# MCU.net
KiCad netlist of a schematic drawn in Altium Designer
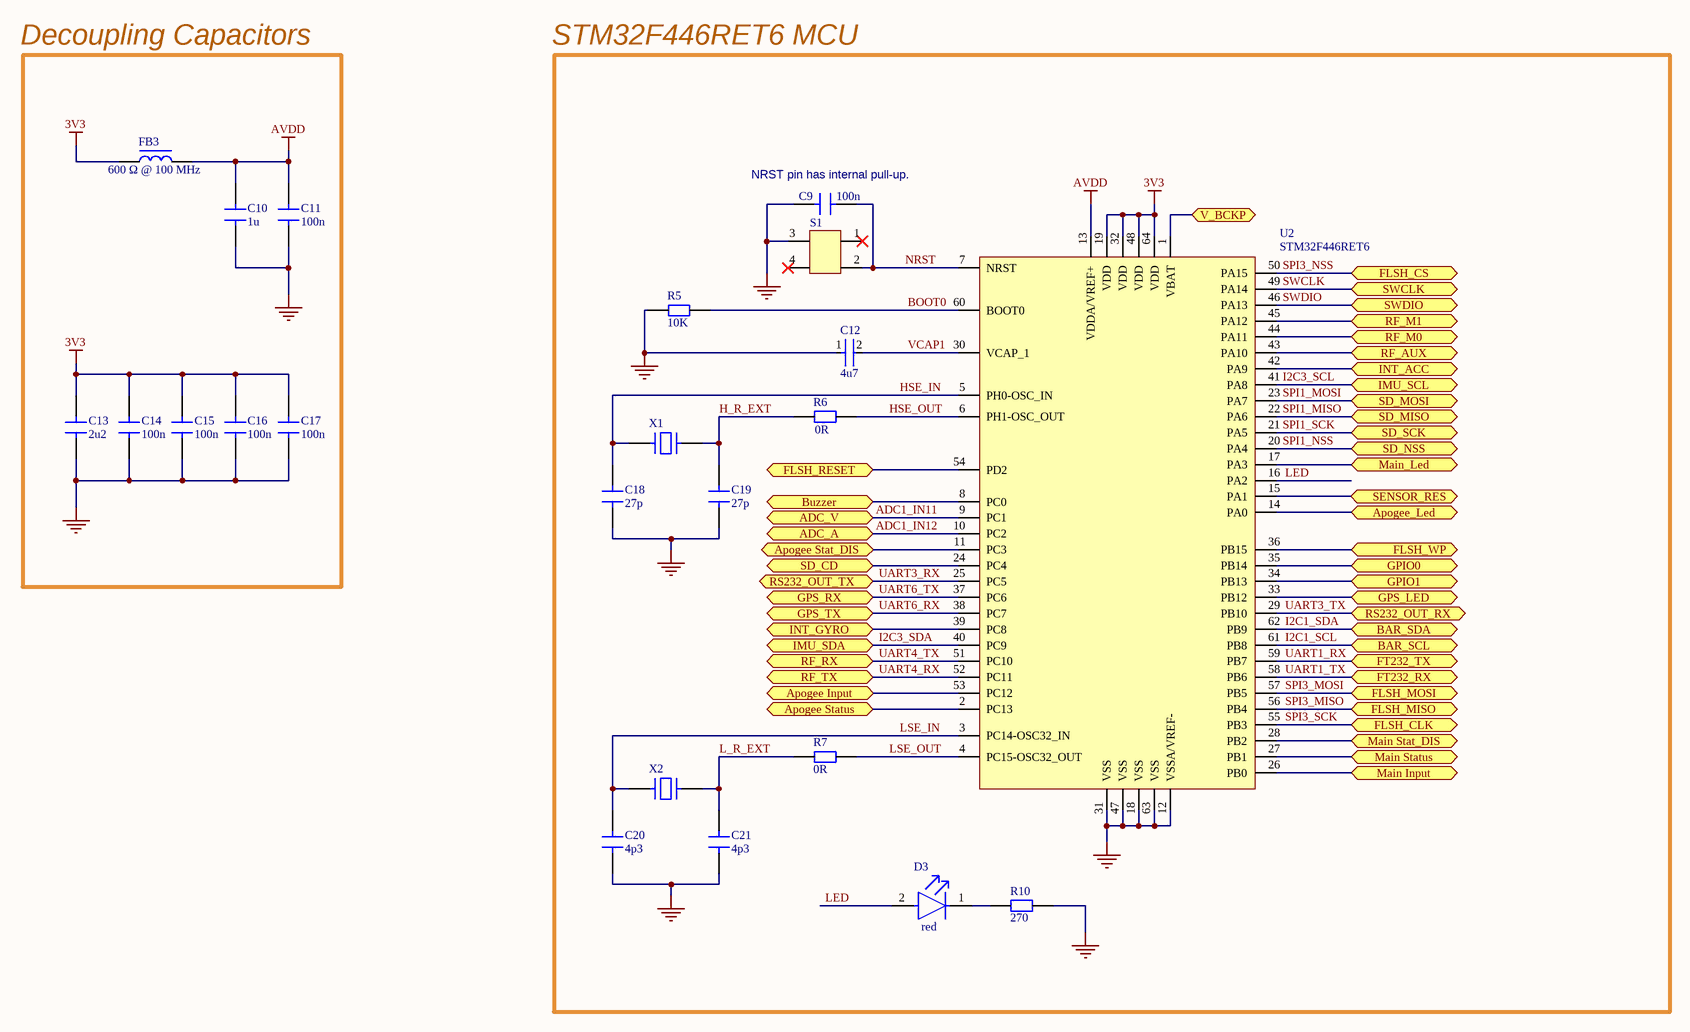
[diagram p0: MCU.SchDoc]

(export (version "E")
  (design (tool "Eeschema 10.0.6"))
  (components
    (comp (ref "C9")
      (value "100n")
      (footprint "CAP 0603")
      (description "Capacitor SMD 0603 50V")
      (libsource (lib "Schlib") (part "CAP 0603 50V"))
    )
    (comp (ref "C10")
      (value "1u")
      (footprint "CAP 0805")
      (description "Capacitor SMD 0805 50V")
      (libsource (lib "Schlib") (part "CAP 0805 50V"))
    )
    (comp (ref "C11")
      (value "100n")
      (footprint "CAP 0805")
      (description "Capacitor SMD 0805 50V")
      (libsource (lib "R_07_24-Schlib") (part "CAP 0805 50V"))
    )
    (comp (ref "C12")
      (value "4u7")
      (footprint "FP-1206-L_3_2_0_2-W_1_6_0-IPC_A")
      (description "None")
      (fields (field (name "TOLERANCE") "20%"))
      (libsource (lib "Altium Content Vault") (part "b4654b650e69147ec39a6b967a45e02"))
    )
    (comp (ref "C13")
      (value "2u2")
      (footprint "CAP 0805")
      (description "Capacitor SMD 0805 25V")
      (libsource (lib "Schlib") (part "CAP 0805 25V"))
    )
    (comp (ref "C14")
      (value "100n")
      (footprint "CAP 0805")
      (description "Capacitor SMD 0805 50V")
      (libsource (lib "R_07_24-Schlib") (part "CAP 0805 50V"))
    )
    (comp (ref "C15")
      (value "100n")
      (footprint "CAP 0805")
      (description "Capacitor SMD 0805 50V")
      (libsource (lib "R_07_24-Schlib") (part "CAP 0805 50V"))
    )
    (comp (ref "C16")
      (value "100n")
      (footprint "CAP 0805")
      (description "Capacitor SMD 0805 50V")
      (libsource (lib "R_07_24-Schlib") (part "CAP 0805 50V"))
    )
    (comp (ref "C17")
      (value "100n")
      (footprint "CAP 0805")
      (description "Capacitor SMD 0805 50V")
      (libsource (lib "R_07_24-Schlib") (part "CAP 0805 50V"))
    )
    (comp (ref "C18")
      (value "27p")
      (footprint "CAP 0805")
      (description "Capacitor SMD 0805 50V")
      (libsource (lib "R_07_24-Schlib") (part "CAP 0805 50V"))
    )
    (comp (ref "C19")
      (value "27p")
      (footprint "CAP 0805")
      (description "Capacitor SMD 0805 50V")
      (libsource (lib "R_07_24-Schlib") (part "CAP 0805 50V"))
    )
    (comp (ref "C20")
      (value "4p3")
      (footprint "CAP 0805")
      (description "Capacitor SMD 0805 50V")
      (libsource (lib "R_07_24-Schlib") (part "CAP 0805 50V"))
    )
    (comp (ref "C21")
      (value "4p3")
      (footprint "CAP 0805")
      (description "Capacitor SMD 0805 50V")
      (libsource (lib "R_07_24-Schlib") (part "CAP 0805 50V"))
    )
    (comp (ref "D3")
      (value "red")
      (footprint "FP-LTST-C170GKT-MFG")
      (description "LED GREEN CLEAR SMD")
      (fields (field (name "VOLTAGE") "5V"))
      (libsource (lib "Altium Content Vault") (part "8706943c75ba83719d021d2fdc84c58"))
    )
    (comp (ref "FB3")
      (value "600 Ω @ 100 MHz")
      (footprint "FB 0805")
      (description "Ferrite Bead SMD 0805")
      (libsource (lib "Schlib") (part "FB 0805"))
    )
    (comp (ref "R5")
      (value "10K")
      (footprint "RES 0805")
      (description "Resistor SMD 0805")
      (libsource (lib "R_07_24-Schlib") (part "RES 0805"))
    )
    (comp (ref "R6")
      (value "0R")
      (footprint "RES 0805")
      (description "Resistor SMD 0805")
      (libsource (lib "R_07_24-Schlib") (part "RES 0805"))
    )
    (comp (ref "R7")
      (value "0R")
      (footprint "RES 0805")
      (description "Resistor SMD 0805")
      (libsource (lib "R_07_24-Schlib") (part "RES 0805"))
    )
    (comp (ref "R10")
      (value "270")
      (footprint "RES 0805")
      (description "Resistor SMD 0805")
      (libsource (lib "R_07_24-Schlib") (part "RES 0805"))
    )
    (comp (ref "S1")
      (value "FSM4JSMATR")
      (footprint "FSM4JSMATR")
      (description "Switch Tactile OFF (ON) SPST Round Button Gull Wing 0.05A 24VDC 1.57N SMD T/R")
      (fields (field (name "MANUFACTURER") "TE Connectivity Alcoswitch"))
      (libsource (lib "Schlib") (part "FSM4JSMATR"))
    )
    (comp (ref "U2")
      (value "STM32F446RET6")
      (footprint "STM32F446RET6")
      (description "ARM® Cortex®-M4 STM32 F4 Microcontroller IC 32-Bit 180MHz 512KB (512K x 8) FLASH 64-LQFP (10x10)")
      (fields (field (name "MANUFACTURER") "STMicroelectronics"))
      (libsource (lib "Schlib") (part "STM32F446RET6"))
    )
    (comp (ref "X1")
      (value "ABM3-8.000MHZ-D2Y-T")
      (footprint "ABM3-8.000MHZ-D2Y-T")
      (description "Crystal 8MHz ±20ppm (Tol) ±30ppm (Stability) 18pF FUND 140Ohm 2-Pin Mini-CSMD T/R")
      (fields (field (name "MANUFACTURER") "Abracon"))
      (libsource (lib "Schlib") (part "ABM3-8.000MHZ-D2Y-T"))
    )
    (comp (ref "X2")
      (value "ABS25-32.768KHZ-6-T")
      (footprint "ABS25-32.768KHZ-6-T")
      (description "Crystal, Plastic Molded 32.768Khz, 6Pf, 20Ppm-40+85C, 8 X 3.8 X 2.5 Rohs Compliant: Yes")
      (fields (field (name "MANUFACTURER") "Abracon"))
      (libsource (lib "Schlib") (part "ABS25-32.768KHZ-6-T"))
    )
  )
  (nets
    (net (code "1") (name "/ADC1_IN11") (class "Default")
      (node (ref "U2") (pin "9") (pinfunction "PC1_9") (pintype "passive"))
    )
    (net (code "2") (name "/ADC1_IN12") (class "Default")
      (node (ref "U2") (pin "10") (pinfunction "PC2_10") (pintype "passive"))
    )
    (net (code "3") (name "/Apogee Input") (class "Default")
      (node (ref "U2") (pin "53") (pinfunction "PC12_53") (pintype "passive"))
    )
    (net (code "4") (name "/Apogee Stat_DIS") (class "Default")
      (node (ref "U2") (pin "11") (pinfunction "PC3_11") (pintype "passive"))
    )
    (net (code "5") (name "/Apogee Status") (class "Default")
      (node (ref "U2") (pin "2") (pinfunction "PC13_2") (pintype "passive"))
    )
    (net (code "6") (name "/Apogee_Led") (class "Default")
      (node (ref "U2") (pin "14") (pinfunction "PA0_14") (pintype "passive"))
    )
    (net (code "7") (name "/BOOT0") (class "Default")
      (node (ref "R5") (pin "2") (pinfunction "2_2") (pintype "passive"))
      (node (ref "U2") (pin "60") (pinfunction "BOOT0_60") (pintype "passive"))
    )
    (net (code "8") (name "/Buzzer") (class "Default")
      (node (ref "U2") (pin "8") (pinfunction "PC0_8") (pintype "passive"))
    )
    (net (code "9") (name "/FLSH_RESET") (class "Default")
      (node (ref "U2") (pin "54") (pinfunction "PD2_54") (pintype "passive"))
    )
    (net (code "10") (name "/FLSH_WP") (class "Default")
      (node (ref "U2") (pin "36") (pinfunction "PB15_36") (pintype "passive"))
    )
    (net (code "11") (name "/GPIO0") (class "Default")
      (node (ref "U2") (pin "35") (pinfunction "PB14_35") (pintype "passive"))
    )
    (net (code "12") (name "/GPIO1") (class "Default")
      (node (ref "U2") (pin "34") (pinfunction "PB13_34") (pintype "passive"))
    )
    (net (code "13") (name "/GPS_LED") (class "Default")
      (node (ref "U2") (pin "33") (pinfunction "PB12_33") (pintype "passive"))
    )
    (net (code "14") (name "/HSE_IN") (class "Default")
      (node (ref "C18") (pin "2") (pinfunction "2_2") (pintype "passive"))
      (node (ref "U2") (pin "5") (pinfunction "PH0-OSC_IN_5") (pintype "passive"))
      (node (ref "X1") (pin "1") (pinfunction "1_1") (pintype "passive"))
    )
    (net (code "15") (name "/HSE_OUT") (class "Default")
      (node (ref "R6") (pin "2") (pinfunction "2_2") (pintype "passive"))
      (node (ref "U2") (pin "6") (pinfunction "PH1-OSC_OUT_6") (pintype "passive"))
    )
    (net (code "16") (name "/H_R_EXT") (class "Default")
      (node (ref "C19") (pin "2") (pinfunction "2_2") (pintype "passive"))
      (node (ref "R6") (pin "1") (pinfunction "1_1") (pintype "passive"))
      (node (ref "X1") (pin "2") (pinfunction "2_2") (pintype "passive"))
    )
    (net (code "17") (name "/I2C1_SCL") (class "Default")
      (node (ref "U2") (pin "61") (pinfunction "PB8_61") (pintype "passive"))
    )
    (net (code "18") (name "/I2C1_SDA") (class "Default")
      (node (ref "U2") (pin "62") (pinfunction "PB9_62") (pintype "passive"))
    )
    (net (code "19") (name "/I2C3_SCL") (class "Default")
      (node (ref "U2") (pin "41") (pinfunction "PA8_41") (pintype "passive"))
    )
    (net (code "20") (name "/I2C3_SDA") (class "Default")
      (node (ref "U2") (pin "40") (pinfunction "PC9_40") (pintype "passive"))
    )
    (net (code "21") (name "/INT_ACC") (class "Default")
      (node (ref "U2") (pin "42") (pinfunction "PA9_42") (pintype "passive"))
    )
    (net (code "22") (name "/INT_GYRO") (class "Default")
      (node (ref "U2") (pin "39") (pinfunction "PC8_39") (pintype "passive"))
    )
    (net (code "23") (name "/LED") (class "Default")
      (node (ref "D3") (pin "2") (pinfunction "A_2") (pintype "passive"))
      (node (ref "U2") (pin "16") (pinfunction "PA2_16") (pintype "passive"))
    )
    (net (code "24") (name "/LSE_IN") (class "Default")
      (node (ref "C20") (pin "2") (pinfunction "2_2") (pintype "passive"))
      (node (ref "U2") (pin "3") (pinfunction "PC14-OSC32_IN_3") (pintype "passive"))
      (node (ref "X2") (pin "1") (pinfunction "1_1") (pintype "passive"))
    )
    (net (code "25") (name "/LSE_OUT") (class "Default")
      (node (ref "R7") (pin "2") (pinfunction "2_2") (pintype "passive"))
      (node (ref "U2") (pin "4") (pinfunction "PC15-OSC32_OUT_4") (pintype "passive"))
    )
    (net (code "26") (name "/L_R_EXT") (class "Default")
      (node (ref "C21") (pin "2") (pinfunction "2_2") (pintype "passive"))
      (node (ref "R7") (pin "1") (pinfunction "1_1") (pintype "passive"))
      (node (ref "X2") (pin "4") (pinfunction "4_4") (pintype "passive"))
    )
    (net (code "27") (name "/Main Input") (class "Default")
      (node (ref "U2") (pin "26") (pinfunction "PB0_26") (pintype "passive"))
    )
    (net (code "28") (name "/Main Stat_DIS") (class "Default")
      (node (ref "U2") (pin "28") (pinfunction "PB2_28") (pintype "passive"))
    )
    (net (code "29") (name "/Main Status") (class "Default")
      (node (ref "U2") (pin "27") (pinfunction "PB1_27") (pintype "passive"))
    )
    (net (code "30") (name "/Main_Led") (class "Default")
      (node (ref "U2") (pin "17") (pinfunction "PA3_17") (pintype "passive"))
    )
    (net (code "31") (name "/NRST") (class "Default")
      (node (ref "C9") (pin "2") (pinfunction "2_2") (pintype "passive"))
      (node (ref "S1") (pin "2") (pinfunction "2_2") (pintype "passive"))
      (node (ref "U2") (pin "7") (pinfunction "NRST_7") (pintype "passive"))
    )
    (net (code "32") (name "/RF_AUX") (class "Default")
      (node (ref "U2") (pin "43") (pinfunction "PA10_43") (pintype "passive"))
    )
    (net (code "33") (name "/RF_M0") (class "Default")
      (node (ref "U2") (pin "44") (pinfunction "PA11_44") (pintype "passive"))
    )
    (net (code "34") (name "/RF_M1") (class "Default")
      (node (ref "U2") (pin "45") (pinfunction "PA12_45") (pintype "passive"))
    )
    (net (code "35") (name "/SD_CD") (class "Default")
      (node (ref "U2") (pin "24") (pinfunction "PC4_24") (pintype "passive"))
    )
    (net (code "36") (name "/SENSOR_RES") (class "Default")
      (node (ref "U2") (pin "15") (pinfunction "PA1_15") (pintype "passive"))
    )
    (net (code "37") (name "/SPI1_MISO") (class "Default")
      (node (ref "U2") (pin "22") (pinfunction "PA6_22") (pintype "passive"))
    )
    (net (code "38") (name "/SPI1_MOSI") (class "Default")
      (node (ref "U2") (pin "23") (pinfunction "PA7_23") (pintype "passive"))
    )
    (net (code "39") (name "/SPI1_NSS") (class "Default")
      (node (ref "U2") (pin "20") (pinfunction "PA4_20") (pintype "passive"))
    )
    (net (code "40") (name "/SPI1_SCK") (class "Default")
      (node (ref "U2") (pin "21") (pinfunction "PA5_21") (pintype "passive"))
    )
    (net (code "41") (name "/SPI3_MISO") (class "Default")
      (node (ref "U2") (pin "56") (pinfunction "PB4_56") (pintype "passive"))
    )
    (net (code "42") (name "/SPI3_MOSI") (class "Default")
      (node (ref "U2") (pin "57") (pinfunction "PB5_57") (pintype "passive"))
    )
    (net (code "43") (name "/SPI3_NSS") (class "Default")
      (node (ref "U2") (pin "50") (pinfunction "PA15_50") (pintype "passive"))
    )
    (net (code "44") (name "/SPI3_SCK") (class "Default")
      (node (ref "U2") (pin "55") (pinfunction "PB3_55") (pintype "passive"))
    )
    (net (code "45") (name "/SWCLK") (class "Default")
      (node (ref "U2") (pin "49") (pinfunction "PA14_49") (pintype "passive"))
    )
    (net (code "46") (name "/SWDIO") (class "Default")
      (node (ref "U2") (pin "46") (pinfunction "PA13_46") (pintype "passive"))
    )
    (net (code "47") (name "/UART1_RX") (class "Default")
      (node (ref "U2") (pin "59") (pinfunction "PB7_59") (pintype "passive"))
    )
    (net (code "48") (name "/UART1_TX") (class "Default")
      (node (ref "U2") (pin "58") (pinfunction "PB6_58") (pintype "passive"))
    )
    (net (code "49") (name "/UART3_RX") (class "Default")
      (node (ref "U2") (pin "25") (pinfunction "PC5_25") (pintype "passive"))
    )
    (net (code "50") (name "/UART3_TX") (class "Default")
      (node (ref "U2") (pin "29") (pinfunction "PB10_29") (pintype "passive"))
    )
    (net (code "51") (name "/UART4_RX") (class "Default")
      (node (ref "U2") (pin "52") (pinfunction "PC11_52") (pintype "passive"))
    )
    (net (code "52") (name "/UART4_TX") (class "Default")
      (node (ref "U2") (pin "51") (pinfunction "PC10_51") (pintype "passive"))
    )
    (net (code "53") (name "/UART6_RX") (class "Default")
      (node (ref "U2") (pin "38") (pinfunction "PC7_38") (pintype "passive"))
    )
    (net (code "54") (name "/UART6_TX") (class "Default")
      (node (ref "U2") (pin "37") (pinfunction "PC6_37") (pintype "passive"))
    )
    (net (code "55") (name "/VCAP1") (class "Default")
      (node (ref "C12") (pin "2") (pinfunction "2_2") (pintype "passive"))
      (node (ref "U2") (pin "30") (pinfunction "VCAP_1_30") (pintype "passive"))
    )
    (net (code "56") (name "/V_BCKP") (class "Default")
      (node (ref "U2") (pin "1") (pinfunction "VBAT_1") (pintype "passive"))
    )
    (net (code "57") (name "3V3") (class "Default")
      (node (ref "C13") (pin "2") (pinfunction "2_2") (pintype "passive"))
      (node (ref "C14") (pin "2") (pinfunction "2_2") (pintype "passive"))
      (node (ref "C15") (pin "2") (pinfunction "2_2") (pintype "passive"))
      (node (ref "C16") (pin "2") (pinfunction "2_2") (pintype "passive"))
      (node (ref "C17") (pin "2") (pinfunction "2_2") (pintype "passive"))
      (node (ref "FB3") (pin "1") (pintype "passive"))
      (node (ref "U2") (pin "19") (pinfunction "VDD_19") (pintype "passive"))
      (node (ref "U2") (pin "32") (pinfunction "VDD_32") (pintype "passive"))
      (node (ref "U2") (pin "48") (pinfunction "VDD_48") (pintype "passive"))
      (node (ref "U2") (pin "64") (pinfunction "VDD_64") (pintype "passive"))
    )
    (net (code "58") (name "AVDD") (class "Default")
      (node (ref "C10") (pin "2") (pinfunction "2_2") (pintype "passive"))
      (node (ref "C11") (pin "2") (pinfunction "2_2") (pintype "passive"))
      (node (ref "FB3") (pin "2") (pintype "passive"))
      (node (ref "U2") (pin "13") (pinfunction "VDDA/VREF+_13") (pintype "passive"))
    )
    (net (code "59") (name "GND") (class "Default")
      (node (ref "C10") (pin "1") (pinfunction "1_1") (pintype "passive"))
      (node (ref "C11") (pin "1") (pinfunction "1_1") (pintype "passive"))
      (node (ref "C12") (pin "1") (pinfunction "1_1") (pintype "passive"))
      (node (ref "C13") (pin "1") (pinfunction "1_1") (pintype "passive"))
      (node (ref "C14") (pin "1") (pinfunction "1_1") (pintype "passive"))
      (node (ref "C15") (pin "1") (pinfunction "1_1") (pintype "passive"))
      (node (ref "C16") (pin "1") (pinfunction "1_1") (pintype "passive"))
      (node (ref "C17") (pin "1") (pinfunction "1_1") (pintype "passive"))
      (node (ref "C18") (pin "1") (pinfunction "1_1") (pintype "passive"))
      (node (ref "C19") (pin "1") (pinfunction "1_1") (pintype "passive"))
      (node (ref "C20") (pin "1") (pinfunction "1_1") (pintype "passive"))
      (node (ref "C21") (pin "1") (pinfunction "1_1") (pintype "passive"))
      (node (ref "C9") (pin "1") (pinfunction "1_1") (pintype "passive"))
      (node (ref "R10") (pin "1") (pinfunction "1_1") (pintype "passive"))
      (node (ref "R5") (pin "1") (pinfunction "1_1") (pintype "passive"))
      (node (ref "S1") (pin "3") (pinfunction "3_3") (pintype "passive"))
      (node (ref "U2") (pin "12") (pinfunction "VSSA/VREF-_12") (pintype "passive"))
      (node (ref "U2") (pin "18") (pinfunction "VSS_18") (pintype "passive"))
      (node (ref "U2") (pin "31") (pinfunction "VSS_31") (pintype "passive"))
      (node (ref "U2") (pin "47") (pinfunction "VSS_47") (pintype "passive"))
      (node (ref "U2") (pin "63") (pinfunction "VSS_63") (pintype "passive"))
    )
    (net (code "60") (name "Net-(D3-C)") (class "Default")
      (node (ref "D3") (pin "1") (pinfunction "C_1") (pintype "passive"))
      (node (ref "R10") (pin "2") (pinfunction "2_2") (pintype "passive"))
    )
    (net (code "61") (name "unconnected-(S1-Pad1)") (class "Default")
      (node (ref "S1") (pin "1") (pinfunction "1_1") (pintype "passive+no_connect"))
    )
    (net (code "62") (name "unconnected-(S1-Pad4)") (class "Default")
      (node (ref "S1") (pin "4") (pinfunction "4_4") (pintype "passive+no_connect"))
    )
  )
)
